# FanControl.net
KiCad netlist of a schematic drawn in EAGLE
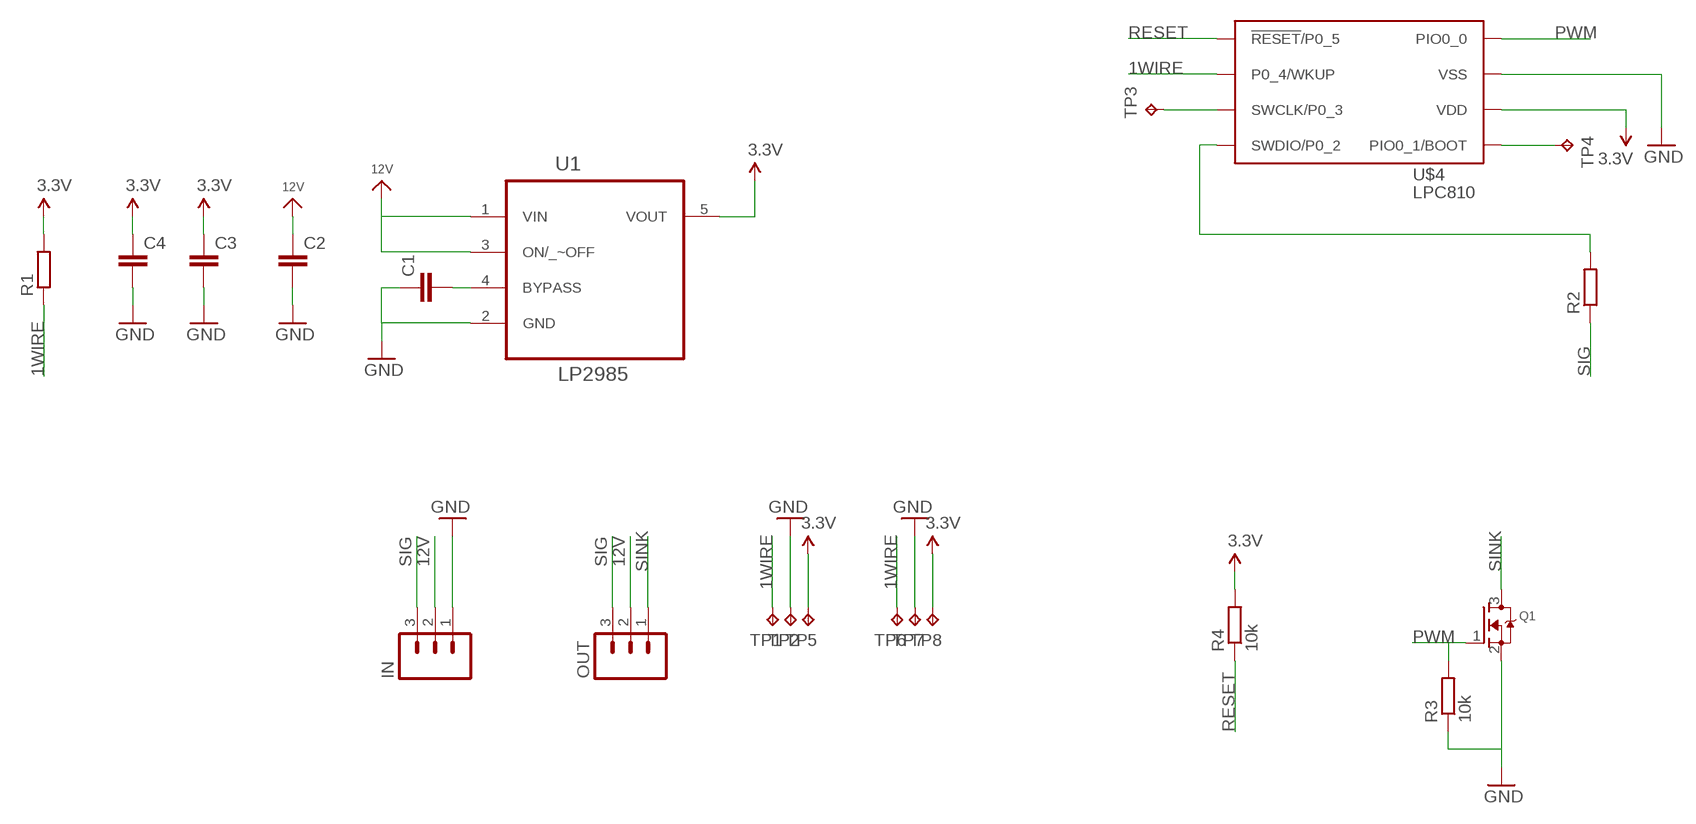
[diagram p0: schematic, sheet 1]

(export (version "E")
  (design (tool "Eeschema 10.0.6"))
  (components
    (comp (ref "C1")
      (value "C-EUC0603")
      (footprint "eagle-import:C0603")
      (libsource (lib "eagle-import") (part "C-EUC0603"))
    )
    (comp (ref "C2")
      (value "C-EUC0805")
      (footprint "eagle-import:C0805")
      (libsource (lib "eagle-import") (part "C-EUC0805"))
    )
    (comp (ref "C3")
      (value "C-EUC0603")
      (footprint "eagle-import:C0603")
      (libsource (lib "eagle-import") (part "C-EUC0603"))
    )
    (comp (ref "C4")
      (value "C-EUC0805")
      (footprint "eagle-import:C0805")
      (libsource (lib "eagle-import") (part "C-EUC0805"))
    )
    (comp (ref "IN")
      (value "M03PTH")
      (footprint "eagle-import:1X03")
      (libsource (lib "eagle-import") (part "M03PTH"))
    )
    (comp (ref "OUT")
      (value "M03PTH")
      (footprint "eagle-import:1X03")
      (libsource (lib "eagle-import") (part "M03PTH"))
    )
    (comp (ref "Q1")
      (value "MOSFET-NREFLOW")
      (footprint "eagle-import:SOT23")
      (libsource (lib "eagle-import") (part "MOSFET-NREFLOW"))
    )
    (comp (ref "R1")
      (value "R-EU_R0603")
      (footprint "eagle-import:R0603")
      (libsource (lib "eagle-import") (part "R-EU_R0603"))
    )
    (comp (ref "R2")
      (value "R-EU_R0603")
      (footprint "eagle-import:R0603")
      (libsource (lib "eagle-import") (part "R-EU_R0603"))
    )
    (comp (ref "R3")
      (value "10k")
      (footprint "eagle-import:R0603")
      (libsource (lib "eagle-import") (part "R-EU_R0603"))
    )
    (comp (ref "R4")
      (value "10k")
      (footprint "eagle-import:R0603")
      (libsource (lib "eagle-import") (part "R-EU_R0603"))
    )
    (comp (ref "TP1")
      (value "TPB1,27")
      (footprint "eagle-import:B1,27")
      (libsource (lib "eagle-import") (part "TPB1,27"))
    )
    (comp (ref "TP2")
      (value "TPB1,27")
      (footprint "eagle-import:B1,27")
      (libsource (lib "eagle-import") (part "TPB1,27"))
    )
    (comp (ref "TP3")
      (value "TPB1,27")
      (footprint "eagle-import:B1,27")
      (libsource (lib "eagle-import") (part "TPB1,27"))
    )
    (comp (ref "TP4")
      (value "TPB1,27")
      (footprint "eagle-import:B1,27")
      (libsource (lib "eagle-import") (part "TPB1,27"))
    )
    (comp (ref "TP5")
      (value "TPB1,27")
      (footprint "eagle-import:B1,27")
      (libsource (lib "eagle-import") (part "TPB1,27"))
    )
    (comp (ref "TP6")
      (value "TPB1,27")
      (footprint "eagle-import:B1,27")
      (libsource (lib "eagle-import") (part "TPB1,27"))
    )
    (comp (ref "TP7")
      (value "TPB1,27")
      (footprint "eagle-import:B1,27")
      (libsource (lib "eagle-import") (part "TPB1,27"))
    )
    (comp (ref "TP8")
      (value "TPB1,27")
      (footprint "eagle-import:B1,27")
      (libsource (lib "eagle-import") (part "TPB1,27"))
    )
    (comp (ref "U$4")
      (value "LPC810")
      (footprint "eagle-import:DIP8")
      (libsource (lib "eagle-import") (part "LPC810M021FN8"))
    )
    (comp (ref "U1")
      (value "LP2985")
      (footprint "eagle-import:SOT95P280X145-5N")
      (fields (field (name "MPN") "LP2985-33DBVT"))
      (libsource (lib "eagle-import") (part "LP2985-33DBVT"))
    )
  )
  (nets
    (net (code "1") (name "/1WIRE") (class "Default")
      (node (ref "R1") (pin "1") (pinfunction "1_1") (pintype "passive"))
      (node (ref "TP1") (pin "TP") (pinfunction "TP_TP") (pintype "input"))
      (node (ref "TP6") (pin "TP") (pinfunction "TP_TP") (pintype "input"))
      (node (ref "U$4") (pin "P$2") (pinfunction "P0_4/WKUP_P$2") (pintype "bidirectional"))
    )
    (net (code "2") (name "/PWM") (class "Default")
      (node (ref "Q1") (pin "1") (pinfunction "G_1") (pintype "bidirectional"))
      (node (ref "R3") (pin "2") (pinfunction "2_2") (pintype "passive"))
      (node (ref "U$4") (pin "P$8") (pinfunction "PIO0_0_P$8") (pintype "bidirectional"))
    )
    (net (code "3") (name "/RESET") (class "Default")
      (node (ref "R4") (pin "1") (pinfunction "1_1") (pintype "passive"))
      (node (ref "U$4") (pin "P$1") (pinfunction "~{RESET}/P0_5_P$1") (pintype "bidirectional"))
    )
    (net (code "4") (name "/SIG") (class "Default")
      (node (ref "IN") (pin "3") (pinfunction "3_3") (pintype "passive"))
      (node (ref "OUT") (pin "3") (pinfunction "3_3") (pintype "passive"))
      (node (ref "R2") (pin "1") (pinfunction "1_1") (pintype "passive"))
    )
    (net (code "5") (name "/SINK") (class "Default")
      (node (ref "OUT") (pin "1") (pinfunction "1_1") (pintype "passive"))
      (node (ref "Q1") (pin "3") (pinfunction "D_3") (pintype "bidirectional"))
    )
    (net (code "6") (name "3.3V") (class "Default")
      (node (ref "C3") (pin "1") (pinfunction "1_1") (pintype "passive"))
      (node (ref "C4") (pin "1") (pinfunction "1_1") (pintype "passive"))
      (node (ref "R1") (pin "2") (pinfunction "2_2") (pintype "passive"))
      (node (ref "R4") (pin "2") (pinfunction "2_2") (pintype "passive"))
      (node (ref "TP5") (pin "TP") (pinfunction "TP_TP") (pintype "input"))
      (node (ref "TP8") (pin "TP") (pinfunction "TP_TP") (pintype "input"))
      (node (ref "U$4") (pin "P$6") (pinfunction "VDD_P$6") (pintype "bidirectional"))
      (node (ref "U1") (pin "5") (pinfunction "VOUT_5") (pintype "output"))
    )
    (net (code "7") (name "12V") (class "Default")
      (node (ref "C2") (pin "1") (pinfunction "1_1") (pintype "passive"))
      (node (ref "IN") (pin "2") (pinfunction "2_2") (pintype "passive"))
      (node (ref "OUT") (pin "2") (pinfunction "2_2") (pintype "passive"))
      (node (ref "U1") (pin "1") (pinfunction "VIN_1") (pintype "power_in"))
      (node (ref "U1") (pin "3") (pinfunction "ON/_~{OFF}_3") (pintype "input"))
    )
    (net (code "8") (name "GND") (class "Default")
      (node (ref "C1") (pin "1") (pinfunction "1_1") (pintype "passive"))
      (node (ref "C2") (pin "2") (pinfunction "2_2") (pintype "passive"))
      (node (ref "C3") (pin "2") (pinfunction "2_2") (pintype "passive"))
      (node (ref "C4") (pin "2") (pinfunction "2_2") (pintype "passive"))
      (node (ref "IN") (pin "1") (pinfunction "1_1") (pintype "passive"))
      (node (ref "Q1") (pin "2") (pinfunction "S_2") (pintype "bidirectional"))
      (node (ref "R3") (pin "1") (pinfunction "1_1") (pintype "passive"))
      (node (ref "TP2") (pin "TP") (pinfunction "TP_TP") (pintype "input"))
      (node (ref "TP7") (pin "TP") (pinfunction "TP_TP") (pintype "input"))
      (node (ref "U$4") (pin "P$7") (pinfunction "VSS_P$7") (pintype "bidirectional"))
      (node (ref "U1") (pin "2") (pinfunction "GND_2") (pintype "passive"))
    )
    (net (code "9") (name "Net-(U$4-PIO0_1{slash}BOOT)") (class "Default")
      (node (ref "TP4") (pin "TP") (pinfunction "TP_TP") (pintype "input"))
      (node (ref "U$4") (pin "P$5") (pinfunction "PIO0_1/BOOT_P$5") (pintype "bidirectional"))
    )
    (net (code "10") (name "Net-(U$4-SWCLK{slash}P0_3)") (class "Default")
      (node (ref "TP3") (pin "TP") (pinfunction "TP_TP") (pintype "input"))
      (node (ref "U$4") (pin "P$3") (pinfunction "SWCLK/P0_3_P$3") (pintype "bidirectional"))
    )
    (net (code "11") (name "Net-(U$4-SWDIO{slash}P0_2)") (class "Default")
      (node (ref "R2") (pin "2") (pinfunction "2_2") (pintype "passive"))
      (node (ref "U$4") (pin "P$4") (pinfunction "SWDIO/P0_2_P$4") (pintype "bidirectional"))
    )
    (net (code "12") (name "Net-(U1-BYPASS)") (class "Default")
      (node (ref "C1") (pin "2") (pinfunction "2_2") (pintype "passive"))
      (node (ref "U1") (pin "4") (pinfunction "BYPASS_4") (pintype "input"))
    )
  )
)
